# jill.net
KiCad netlist of a schematic drawn in EAGLE
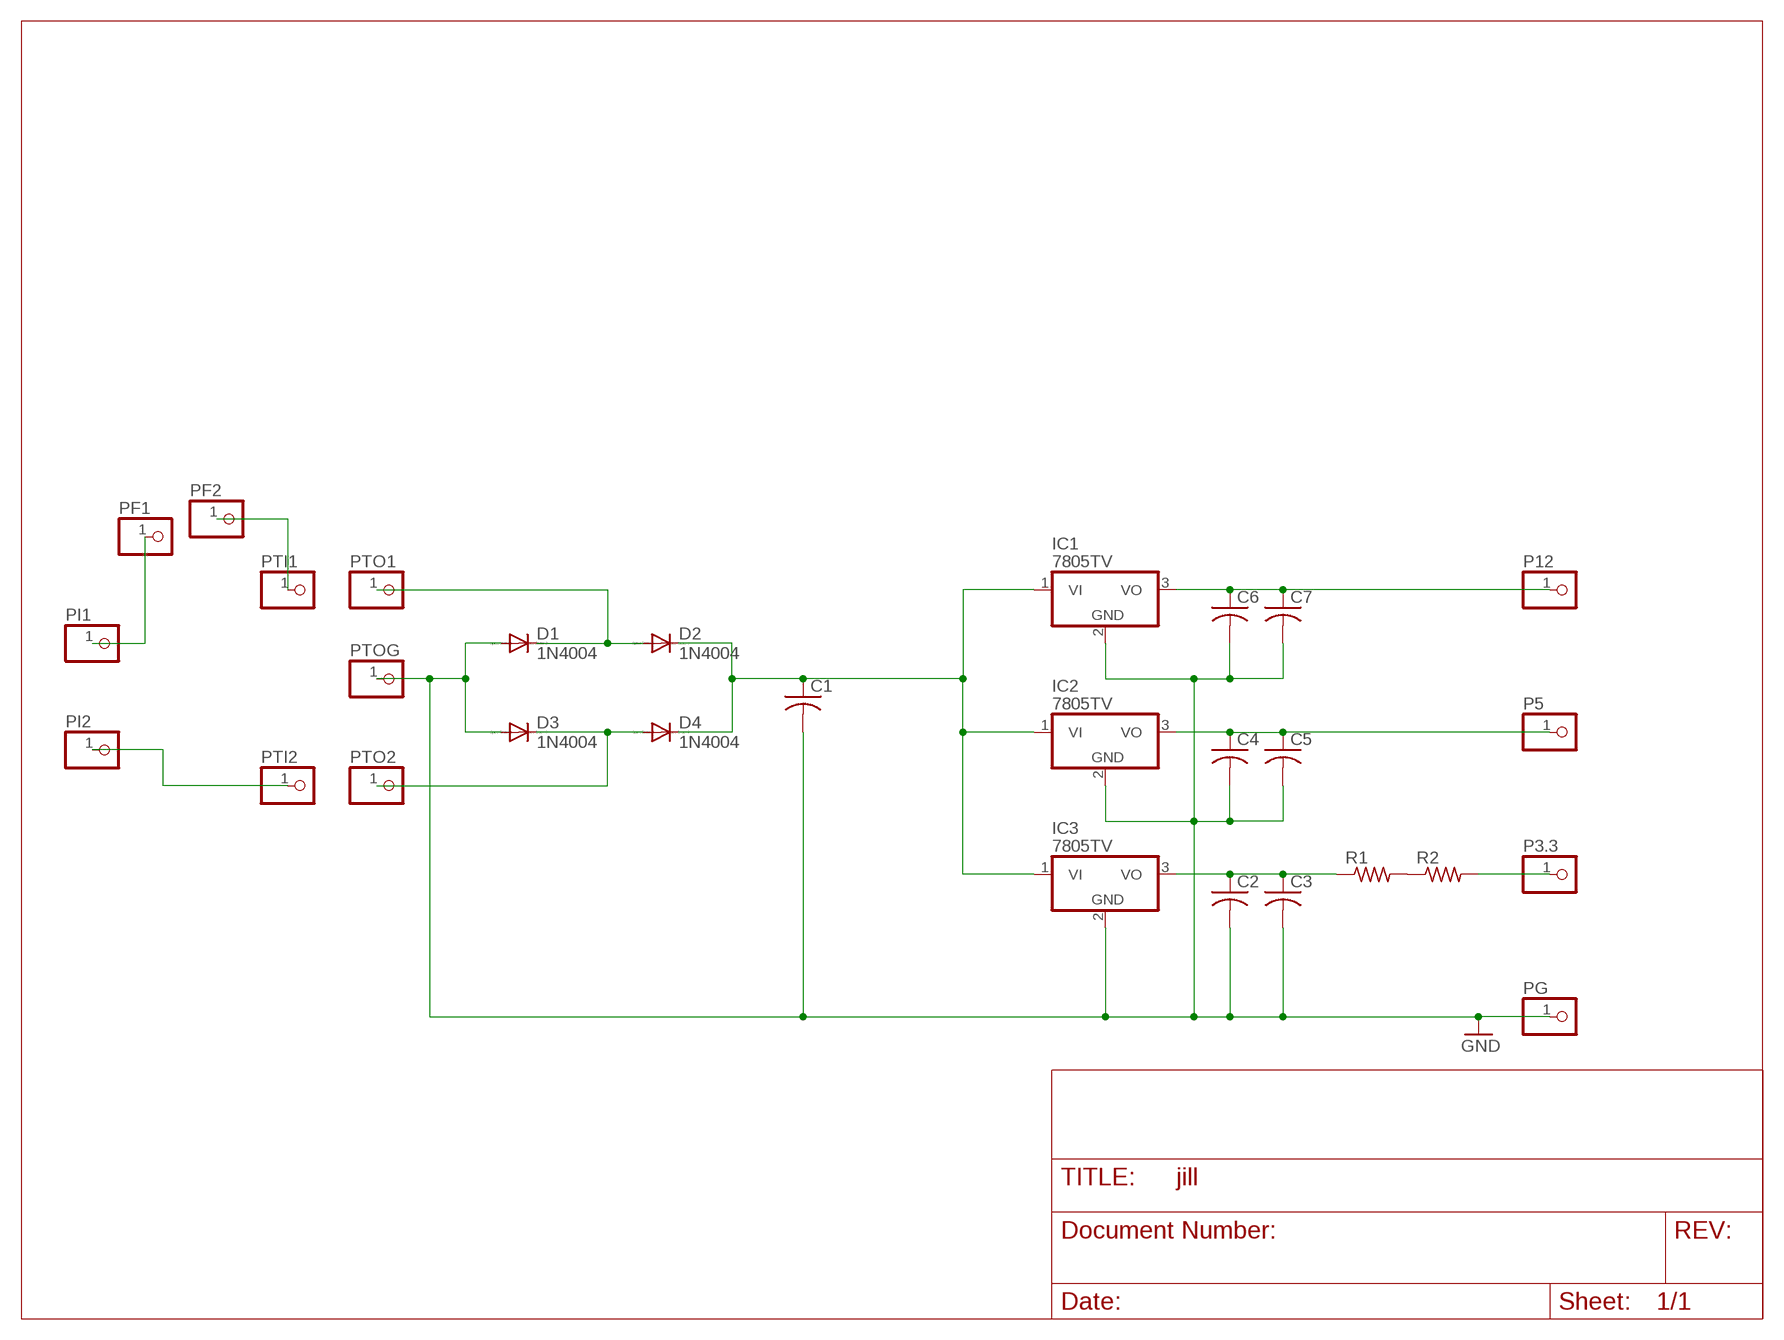
[diagram p0: schematic, sheet 1]

(export (version "E")
  (design (tool "Eeschema 10.0.6"))
  (components
    (comp (ref "C1")
      (value "C-US050-075X075")
      (footprint "eagle-import:C050-075X075")
      (libsource (lib "eagle-import") (part "C-US050-075X075"))
    )
    (comp (ref "C2")
      (value "C-US025-025X050")
      (footprint "eagle-import:C025-025X050")
      (libsource (lib "eagle-import") (part "C-US025-025X050"))
    )
    (comp (ref "C3")
      (value "C-US025-025X050")
      (footprint "eagle-import:C025-025X050")
      (libsource (lib "eagle-import") (part "C-US025-025X050"))
    )
    (comp (ref "C4")
      (value "C-US025-025X050")
      (footprint "eagle-import:C025-025X050")
      (libsource (lib "eagle-import") (part "C-US025-025X050"))
    )
    (comp (ref "C5")
      (value "C-US025-025X050")
      (footprint "eagle-import:C025-025X050")
      (libsource (lib "eagle-import") (part "C-US025-025X050"))
    )
    (comp (ref "C6")
      (value "C-US025-025X050")
      (footprint "eagle-import:C025-025X050")
      (libsource (lib "eagle-import") (part "C-US025-025X050"))
    )
    (comp (ref "C7")
      (value "C-US025-025X050")
      (footprint "eagle-import:C025-025X050")
      (libsource (lib "eagle-import") (part "C-US025-025X050"))
    )
    (comp (ref "D1")
      (value "1N4004")
      (footprint "eagle-import:DO41-10")
      (libsource (lib "eagle-import") (part "1N4004"))
    )
    (comp (ref "D2")
      (value "1N4004")
      (footprint "eagle-import:DO41-10")
      (libsource (lib "eagle-import") (part "1N4004"))
    )
    (comp (ref "D3")
      (value "1N4004")
      (footprint "eagle-import:DO41-10")
      (libsource (lib "eagle-import") (part "1N4004"))
    )
    (comp (ref "D4")
      (value "1N4004")
      (footprint "eagle-import:DO41-10")
      (libsource (lib "eagle-import") (part "1N4004"))
    )
    (comp (ref "IC1")
      (value "7805TV")
      (footprint "eagle-import:TO220V")
      (libsource (lib "eagle-import") (part "78TV05"))
    )
    (comp (ref "IC2")
      (value "7805TV")
      (footprint "eagle-import:TO220V")
      (libsource (lib "eagle-import") (part "78TV05"))
    )
    (comp (ref "IC3")
      (value "7805TV")
      (footprint "eagle-import:TO220V")
      (libsource (lib "eagle-import") (part "78TV05"))
    )
    (comp (ref "P3.3")
      (value "PINHD-1X1")
      (footprint "eagle-import:1X01")
      (libsource (lib "eagle-import") (part "PINHD-1X1"))
    )
    (comp (ref "P5")
      (value "PINHD-1X1")
      (footprint "eagle-import:1X01")
      (libsource (lib "eagle-import") (part "PINHD-1X1"))
    )
    (comp (ref "P12")
      (value "PINHD-1X1")
      (footprint "eagle-import:1X01")
      (libsource (lib "eagle-import") (part "PINHD-1X1"))
    )
    (comp (ref "PF1")
      (value "PINHD-1X1")
      (footprint "eagle-import:1X01")
      (libsource (lib "eagle-import") (part "PINHD-1X1"))
    )
    (comp (ref "PF2")
      (value "PINHD-1X1")
      (footprint "eagle-import:1X01")
      (libsource (lib "eagle-import") (part "PINHD-1X1"))
    )
    (comp (ref "PG")
      (value "PINHD-1X1")
      (footprint "eagle-import:1X01")
      (libsource (lib "eagle-import") (part "PINHD-1X1"))
    )
    (comp (ref "PI1")
      (value "PINHD-1X1")
      (footprint "eagle-import:1X01")
      (libsource (lib "eagle-import") (part "PINHD-1X1"))
    )
    (comp (ref "PI2")
      (value "PINHD-1X1")
      (footprint "eagle-import:1X01")
      (libsource (lib "eagle-import") (part "PINHD-1X1"))
    )
    (comp (ref "PTI1")
      (value "PINHD-1X1")
      (footprint "eagle-import:1X01")
      (libsource (lib "eagle-import") (part "PINHD-1X1"))
    )
    (comp (ref "PTI2")
      (value "PINHD-1X1")
      (footprint "eagle-import:1X01")
      (libsource (lib "eagle-import") (part "PINHD-1X1"))
    )
    (comp (ref "PTO1")
      (value "PINHD-1X1")
      (footprint "eagle-import:1X01")
      (libsource (lib "eagle-import") (part "PINHD-1X1"))
    )
    (comp (ref "PTO2")
      (value "PINHD-1X1")
      (footprint "eagle-import:1X01")
      (libsource (lib "eagle-import") (part "PINHD-1X1"))
    )
    (comp (ref "PTOG")
      (value "PINHD-1X1")
      (footprint "eagle-import:1X01")
      (libsource (lib "eagle-import") (part "PINHD-1X1"))
    )
    (comp (ref "R1")
      (value "R-US_0207/12")
      (footprint "eagle-import:0207_12")
      (libsource (lib "eagle-import") (part "R-US_0207/12"))
    )
    (comp (ref "R2")
      (value "R-US_0207/12")
      (footprint "eagle-import:0207_12")
      (libsource (lib "eagle-import") (part "R-US_0207/12"))
    )
  )
  (nets
    (net (code "1") (name "GND") (class "Default")
      (node (ref "C1") (pin "2") (pinfunction "2_2") (pintype "passive"))
      (node (ref "C2") (pin "2") (pinfunction "2_2") (pintype "passive"))
      (node (ref "C3") (pin "2") (pinfunction "2_2") (pintype "passive"))
      (node (ref "C4") (pin "2") (pinfunction "2_2") (pintype "passive"))
      (node (ref "C5") (pin "2") (pinfunction "2_2") (pintype "passive"))
      (node (ref "C6") (pin "2") (pinfunction "2_2") (pintype "passive"))
      (node (ref "C7") (pin "2") (pinfunction "2_2") (pintype "passive"))
      (node (ref "D1") (pin "A") (pinfunction "A_A") (pintype "passive"))
      (node (ref "D3") (pin "A") (pinfunction "A_A") (pintype "passive"))
      (node (ref "IC1") (pin "2") (pinfunction "GND_2") (pintype "passive"))
      (node (ref "IC2") (pin "2") (pinfunction "GND_2") (pintype "passive"))
      (node (ref "IC3") (pin "2") (pinfunction "GND_2") (pintype "passive"))
      (node (ref "PG") (pin "1") (pinfunction "1_1") (pintype "passive"))
      (node (ref "PTOG") (pin "1") (pinfunction "1_1") (pintype "passive"))
    )
    (net (code "2") (name "Net-(D1-PadC)") (class "Default")
      (node (ref "D1") (pin "C") (pinfunction "C_C") (pintype "passive"))
      (node (ref "D2") (pin "A") (pinfunction "A_A") (pintype "passive"))
      (node (ref "PTO1") (pin "1") (pinfunction "1_1") (pintype "passive"))
    )
    (net (code "3") (name "Net-(D3-PadC)") (class "Default")
      (node (ref "D3") (pin "C") (pinfunction "C_C") (pintype "passive"))
      (node (ref "D4") (pin "A") (pinfunction "A_A") (pintype "passive"))
      (node (ref "PTO2") (pin "1") (pinfunction "1_1") (pintype "passive"))
    )
    (net (code "4") (name "Net-(IC1-VI)") (class "Default")
      (node (ref "C1") (pin "1") (pinfunction "1_1") (pintype "passive"))
      (node (ref "D2") (pin "C") (pinfunction "C_C") (pintype "passive"))
      (node (ref "D4") (pin "C") (pinfunction "C_C") (pintype "passive"))
      (node (ref "IC1") (pin "1") (pinfunction "VI_1") (pintype "input"))
      (node (ref "IC2") (pin "1") (pinfunction "VI_1") (pintype "input"))
      (node (ref "IC3") (pin "1") (pinfunction "VI_1") (pintype "input"))
    )
    (net (code "5") (name "Net-(IC1-VO)") (class "Default")
      (node (ref "C6") (pin "1") (pinfunction "1_1") (pintype "passive"))
      (node (ref "C7") (pin "1") (pinfunction "1_1") (pintype "passive"))
      (node (ref "IC1") (pin "3") (pinfunction "VO_3") (pintype "passive"))
      (node (ref "P12") (pin "1") (pinfunction "1_1") (pintype "passive"))
    )
    (net (code "6") (name "Net-(IC2-VO)") (class "Default")
      (node (ref "C4") (pin "1") (pinfunction "1_1") (pintype "passive"))
      (node (ref "C5") (pin "1") (pinfunction "1_1") (pintype "passive"))
      (node (ref "IC2") (pin "3") (pinfunction "VO_3") (pintype "passive"))
      (node (ref "P5") (pin "1") (pinfunction "1_1") (pintype "passive"))
    )
    (net (code "7") (name "Net-(IC3-VO)") (class "Default")
      (node (ref "C2") (pin "1") (pinfunction "1_1") (pintype "passive"))
      (node (ref "C3") (pin "1") (pinfunction "1_1") (pintype "passive"))
      (node (ref "IC3") (pin "3") (pinfunction "VO_3") (pintype "passive"))
      (node (ref "R1") (pin "1") (pinfunction "1_1") (pintype "passive"))
    )
    (net (code "8") (name "Net-(P3.3-Pad1)") (class "Default")
      (node (ref "P3.3") (pin "1") (pinfunction "1_1") (pintype "passive"))
      (node (ref "R2") (pin "2") (pinfunction "2_2") (pintype "passive"))
    )
    (net (code "9") (name "Net-(PF1-Pad1)") (class "Default")
      (node (ref "PF1") (pin "1") (pinfunction "1_1") (pintype "passive"))
      (node (ref "PI1") (pin "1") (pinfunction "1_1") (pintype "passive"))
    )
    (net (code "10") (name "Net-(PF2-Pad1)") (class "Default")
      (node (ref "PF2") (pin "1") (pinfunction "1_1") (pintype "passive"))
      (node (ref "PTI1") (pin "1") (pinfunction "1_1") (pintype "passive"))
    )
    (net (code "11") (name "Net-(PI2-Pad1)") (class "Default")
      (node (ref "PI2") (pin "1") (pinfunction "1_1") (pintype "passive"))
      (node (ref "PTI2") (pin "1") (pinfunction "1_1") (pintype "passive"))
    )
    (net (code "12") (name "Net-(R1-Pad2)") (class "Default")
      (node (ref "R1") (pin "2") (pinfunction "2_2") (pintype "passive"))
      (node (ref "R2") (pin "1") (pinfunction "1_1") (pintype "passive"))
    )
  )
)
